# Sensorboard.net
KiCad netlist of a schematic drawn in Altium Designer
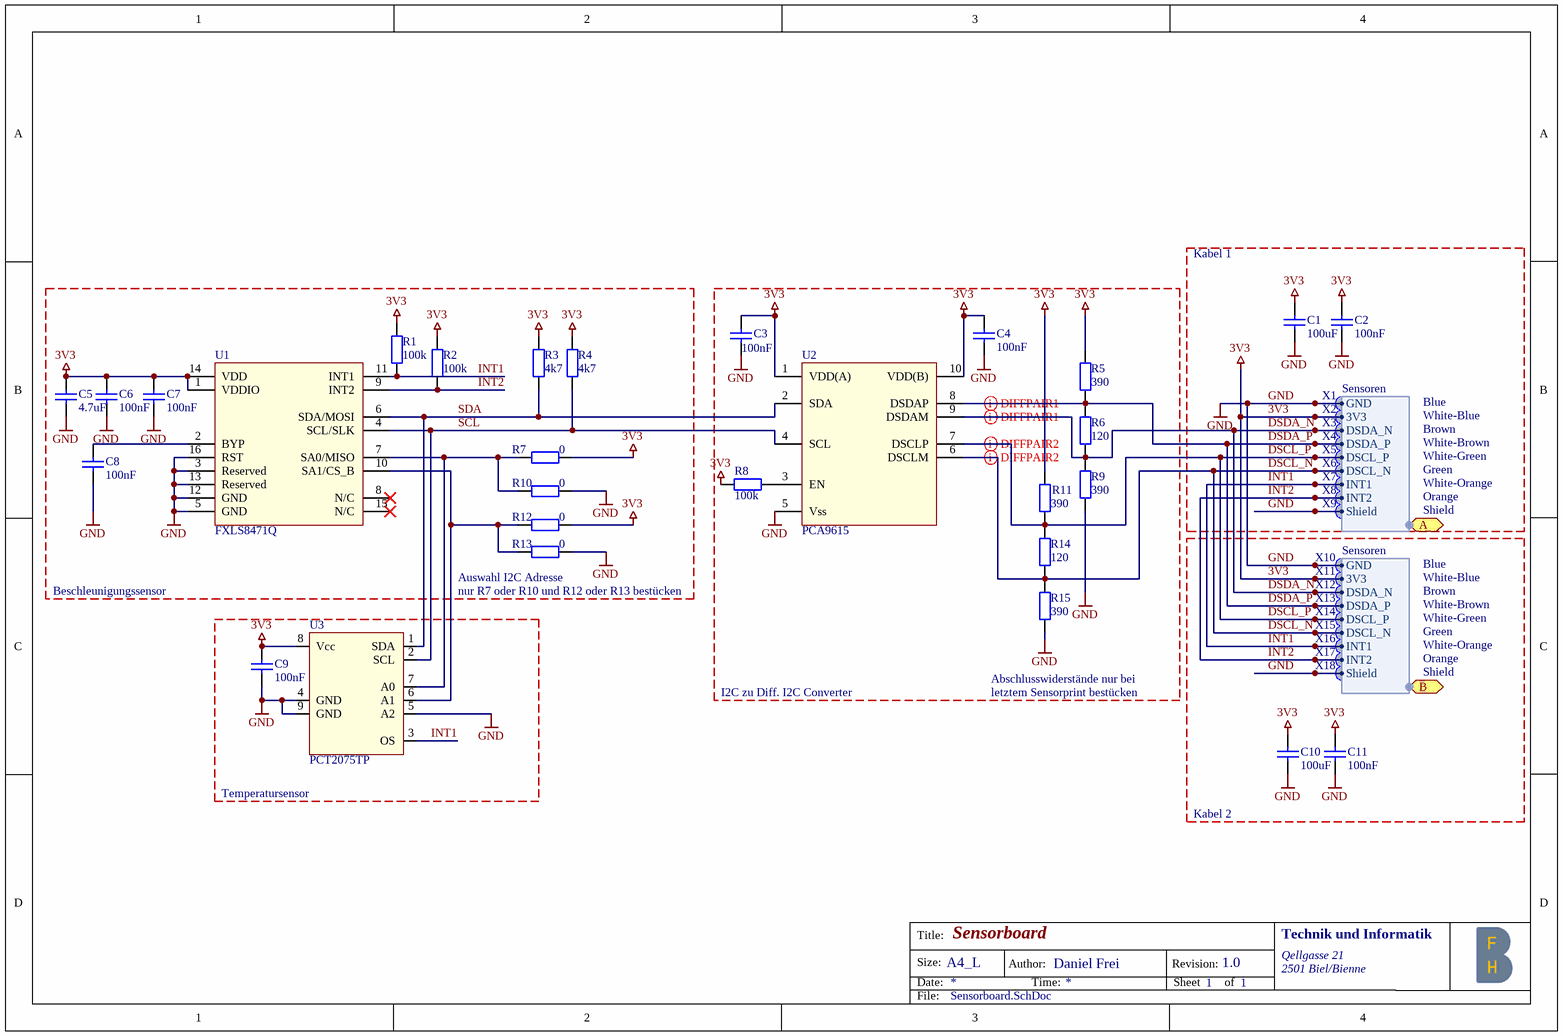
[diagram p0: Sensorboard.SchDoc]

(export (version "E")
  (design (tool "Eeschema 10.0.6"))
  (components
    (comp (ref "C1")
      (value "100uF")
      (footprint "RC_SMD_3D:CAPC3225[1210]X120")
      (description "Capacitor")
      (fields
        (field (name "MANUFACTURER") "Murata")
        (field (name "MANUFACTURER PART NUMBER") "GRM32ER61A107ME20L")
        (field (name "MODIFIED_BY") "BEP1")
      )
      (libsource (lib "RC_SMD_3D") (part "C"))
    )
    (comp (ref "C2")
      (value "100nF")
      (footprint "RC_SMD_3D:CAPC1005[0402]X50")
      (description "Capacitor")
      (fields (field (name "MODIFIED_BY") "BEP1"))
      (libsource (lib "RC_SMD_3D") (part "C"))
    )
    (comp (ref "C3")
      (value "100nF")
      (footprint "RC_SMD_3D:CAPC1005[0402]X50")
      (description "Capacitor")
      (fields (field (name "MODIFIED_BY") "BEP1"))
      (libsource (lib "RC_SMD_3D") (part "C"))
    )
    (comp (ref "C4")
      (value "100nF")
      (footprint "RC_SMD_3D:CAPC1005[0402]X50")
      (description "Capacitor")
      (fields (field (name "MODIFIED_BY") "BEP1"))
      (libsource (lib "RC_SMD_3D") (part "C"))
    )
    (comp (ref "C5")
      (value "4.7uF")
      (footprint "RC_SMD_3D:CAPC1608[0603]X80")
      (description "Capacitor")
      (fields
        (field (name "VOLTAGE") "10V")
        (field (name "MANUFACTURER") "Murata")
        (field (name "MODIFIED_BY") "BEP1")
      )
      (libsource (lib "RC_SMD_3D") (part "C"))
    )
    (comp (ref "C6")
      (value "100nF")
      (footprint "RC_SMD_3D:CAPC1005[0402]X50")
      (description "Capacitor")
      (fields (field (name "MODIFIED_BY") "BEP1"))
      (libsource (lib "RC_SMD_3D") (part "C"))
    )
    (comp (ref "C7")
      (value "100nF")
      (footprint "RC_SMD_3D:CAPC1005[0402]X50")
      (description "Capacitor")
      (fields (field (name "MODIFIED_BY") "BEP1"))
      (libsource (lib "RC_SMD_3D") (part "C"))
    )
    (comp (ref "C8")
      (value "100nF")
      (footprint "RC_SMD_3D:CAPC1005[0402]X50")
      (description "Capacitor")
      (fields (field (name "MODIFIED_BY") "BEP1"))
      (libsource (lib "RC_SMD_3D") (part "C"))
    )
    (comp (ref "C9")
      (value "100nF")
      (footprint "RC_SMD_3D:CAPC1005[0402]X50")
      (description "Capacitor")
      (fields (field (name "MODIFIED_BY") "BEP1"))
      (libsource (lib "RC_SMD_3D") (part "C"))
    )
    (comp (ref "C10")
      (value "100uF")
      (footprint "RC_SMD_3D:CAPC3225[1210]X120")
      (description "Capacitor")
      (fields
        (field (name "MANUFACTURER") "Murata")
        (field (name "MANUFACTURER PART NUMBER") "GRM32ER61A107ME20L")
        (field (name "MODIFIED_BY") "BEP1")
      )
      (libsource (lib "RC_SMD_3D") (part "C"))
    )
    (comp (ref "C11")
      (value "100nF")
      (footprint "RC_SMD_3D:CAPC1005[0402]X50")
      (description "Capacitor")
      (fields (field (name "MODIFIED_BY") "BEP1"))
      (libsource (lib "RC_SMD_3D") (part "C"))
    )
    (comp (ref "R1")
      (value "100k")
      (footprint "RC_SMD_3D:RESC1005[0402]X35")
      (description "Resistor")
      (fields (field (name "MODIFIED_BY") "BEP1"))
      (libsource (lib "RC_SMD_3D") (part "R"))
    )
    (comp (ref "R2")
      (value "100k")
      (footprint "RC_SMD_3D:RESC1005[0402]X35")
      (description "Resistor")
      (fields (field (name "MODIFIED_BY") "BEP1"))
      (libsource (lib "RC_SMD_3D") (part "R"))
    )
    (comp (ref "R3")
      (value "4k7")
      (footprint "RC_SMD_3D:RESC1005[0402]X35")
      (description "Resistor")
      (fields (field (name "MODIFIED_BY") "BEP1"))
      (libsource (lib "RC_SMD_3D") (part "R"))
    )
    (comp (ref "R4")
      (value "4k7")
      (footprint "RC_SMD_3D:RESC1005[0402]X35")
      (description "Resistor")
      (fields (field (name "MODIFIED_BY") "BEP1"))
      (libsource (lib "RC_SMD_3D") (part "R"))
    )
    (comp (ref "R5")
      (value "390")
      (footprint "RC_SMD_3D:RESC1005[0402]X35")
      (description "Resistor")
      (fields (field (name "MODIFIED_BY") "BEP1"))
      (libsource (lib "RC_SMD_3D") (part "R"))
    )
    (comp (ref "R6")
      (value "120")
      (footprint "RC_SMD_3D:RESC1005[0402]X35")
      (description "Resistor")
      (fields (field (name "MODIFIED_BY") "BEP1"))
      (libsource (lib "RC_SMD_3D") (part "R"))
    )
    (comp (ref "R7")
      (value "0")
      (footprint "RC_SMD_3D:RESC1005[0402]X35")
      (description "Resistor")
      (fields
        (field (name "MANUFACTURER") "Panasonic")
        (field (name "MANUFACTURER PART NUMBER") "ERJ-2GE0R00X")
        (field (name "MODIFIED_BY") "BEP1")
      )
      (libsource (lib "") (part "R_1"))
    )
    (comp (ref "R8")
      (value "100k")
      (footprint "RC_SMD_3D:RESC1005[0402]X35")
      (description "Resistor")
      (fields (field (name "MODIFIED_BY") "BEP1"))
      (libsource (lib "") (part "R_1"))
    )
    (comp (ref "R9")
      (value "390")
      (footprint "RC_SMD_3D:RESC1005[0402]X35")
      (description "Resistor")
      (fields (field (name "MODIFIED_BY") "BEP1"))
      (libsource (lib "RC_SMD_3D") (part "R"))
    )
    (comp (ref "R10")
      (value "0")
      (footprint "RC_SMD_3D:RESC1005[0402]X35")
      (description "Resistor")
      (fields
        (field (name "MANUFACTURER") "Panasonic")
        (field (name "MANUFACTURER PART NUMBER") "ERJ-2GE0R00X")
        (field (name "MODIFIED_BY") "BEP1")
      )
      (libsource (lib "") (part "R_1"))
    )
    (comp (ref "R11")
      (value "390")
      (footprint "RC_SMD_3D:RESC1005[0402]X35")
      (description "Resistor")
      (fields (field (name "MODIFIED_BY") "BEP1"))
      (libsource (lib "RC_SMD_3D") (part "R"))
    )
    (comp (ref "R12")
      (value "0")
      (footprint "RC_SMD_3D:RESC1005[0402]X35")
      (description "Resistor")
      (fields
        (field (name "MANUFACTURER") "Panasonic")
        (field (name "MANUFACTURER PART NUMBER") "ERJ-2GE0R00X")
        (field (name "MODIFIED_BY") "BEP1")
      )
      (libsource (lib "") (part "R_1"))
    )
    (comp (ref "R13")
      (value "0")
      (footprint "RC_SMD_3D:RESC1005[0402]X35")
      (description "Resistor")
      (fields
        (field (name "MANUFACTURER") "Panasonic")
        (field (name "MANUFACTURER PART NUMBER") "ERJ-2GE0R00X")
        (field (name "MODIFIED_BY") "BEP1")
      )
      (libsource (lib "") (part "R_1"))
    )
    (comp (ref "R14")
      (value "120")
      (footprint "RC_SMD_3D:RESC1005[0402]X35")
      (description "Resistor")
      (fields (field (name "MODIFIED_BY") "BEP1"))
      (libsource (lib "RC_SMD_3D") (part "R"))
    )
    (comp (ref "R15")
      (value "390")
      (footprint "RC_SMD_3D:RESC1005[0402]X35")
      (description "Resistor")
      (fields (field (name "MODIFIED_BY") "BEP1"))
      (libsource (lib "RC_SMD_3D") (part "R"))
    )
    (comp (ref "U1")
      (value "FXLS8471Q")
      (footprint "16 LEAD QFN")
      (description "3-Axis,  Linear Accelerometer")
      (fields (field (name "MANUFACTURER PART NUMBER") "FXLS8471QR1") (field (name "MANUFACTURER") "NXP"))
      (libsource (lib "Sensorboard_Library") (part "FXLS8471Q"))
    )
    (comp (ref "U2")
      (value "PCA9615")
      (footprint "TSSOP10")
      (description "differential I2C-bus buffer")
      (fields (field (name "MANUFACTURER PART NUMBER") "PCA9615DPJ") (field (name "MANUFACTURER") "NXP"))
      (libsource (lib "Sensorboard_Library") (part "PCA9615"))
    )
    (comp (ref "U3")
      (value "PCT2075TP")
      (footprint "HWSON8")
      (description "Temperature_Sensor")
      (fields (field (name "MANUFACTURER") "NXP") (field (name "MANUFACTURER PART NUMBER") "PCT2075TP,147"))
      (libsource (lib "Sensorboard_Library") (part "PCT2075TP"))
    )
    (comp (ref "X1")
      (value "Loch")
      (footprint "Loch")
      (description "Loch in Print um Kabel einzulöten")
      (libsource (lib "Sensorboard_Library") (part "Loch"))
    )
    (comp (ref "X2")
      (value "Loch")
      (footprint "Loch")
      (description "Loch in Print um Kabel einzulöten")
      (libsource (lib "Sensorboard_Library") (part "Loch"))
    )
    (comp (ref "X3")
      (value "Loch")
      (footprint "Loch")
      (description "Loch in Print um Kabel einzulöten")
      (libsource (lib "Sensorboard_Library") (part "Loch"))
    )
    (comp (ref "X4")
      (value "Loch")
      (footprint "Loch")
      (description "Loch in Print um Kabel einzulöten")
      (libsource (lib "Sensorboard_Library") (part "Loch"))
    )
    (comp (ref "X5")
      (value "Loch")
      (footprint "Loch")
      (description "Loch in Print um Kabel einzulöten")
      (libsource (lib "Sensorboard_Library") (part "Loch"))
    )
    (comp (ref "X6")
      (value "Loch")
      (footprint "Loch")
      (description "Loch in Print um Kabel einzulöten")
      (libsource (lib "Sensorboard_Library") (part "Loch"))
    )
    (comp (ref "X7")
      (value "Loch")
      (footprint "Loch")
      (description "Loch in Print um Kabel einzulöten")
      (libsource (lib "Sensorboard_Library") (part "Loch"))
    )
    (comp (ref "X8")
      (value "Loch")
      (footprint "Loch")
      (description "Loch in Print um Kabel einzulöten")
      (libsource (lib "Sensorboard_Library") (part "Loch"))
    )
    (comp (ref "X9")
      (value "Loch")
      (footprint "Loch")
      (description "Loch in Print um Kabel einzulöten")
      (libsource (lib "Sensorboard_Library") (part "Loch"))
    )
    (comp (ref "X10")
      (value "Loch")
      (footprint "Loch")
      (description "Loch in Print um Kabel einzulöten")
      (libsource (lib "Sensorboard_Library") (part "Loch"))
    )
    (comp (ref "X11")
      (value "Loch")
      (footprint "Loch")
      (description "Loch in Print um Kabel einzulöten")
      (libsource (lib "Sensorboard_Library") (part "Loch"))
    )
    (comp (ref "X12")
      (value "Loch")
      (footprint "Loch")
      (description "Loch in Print um Kabel einzulöten")
      (libsource (lib "Sensorboard_Library") (part "Loch"))
    )
    (comp (ref "X13")
      (value "Loch")
      (footprint "Loch")
      (description "Loch in Print um Kabel einzulöten")
      (libsource (lib "Sensorboard_Library") (part "Loch"))
    )
    (comp (ref "X14")
      (value "Loch")
      (footprint "Loch")
      (description "Loch in Print um Kabel einzulöten")
      (libsource (lib "Sensorboard_Library") (part "Loch"))
    )
    (comp (ref "X15")
      (value "Loch")
      (footprint "Loch")
      (description "Loch in Print um Kabel einzulöten")
      (libsource (lib "Sensorboard_Library") (part "Loch"))
    )
    (comp (ref "X16")
      (value "Loch")
      (footprint "Loch")
      (description "Loch in Print um Kabel einzulöten")
      (libsource (lib "Sensorboard_Library") (part "Loch"))
    )
    (comp (ref "X17")
      (value "Loch")
      (footprint "Loch")
      (description "Loch in Print um Kabel einzulöten")
      (libsource (lib "Sensorboard_Library") (part "Loch"))
    )
    (comp (ref "X18")
      (value "Loch")
      (footprint "Loch")
      (description "Loch in Print um Kabel einzulöten")
      (libsource (lib "Sensorboard_Library") (part "Loch"))
    )
  )
  (nets
    (net (code "2") (name "/DSCL_N") (class "Default")
      (node (ref "R14") (pin "1") (pintype "passive"))
      (node (ref "R15") (pin "2") (pintype "passive"))
      (node (ref "U2") (pin "6") (pinfunction "DSCLM_6") (pintype "passive"))
      (node (ref "X15") (pin "1") (pinfunction "1_1") (pintype "passive"))
      (node (ref "X6") (pin "1") (pinfunction "1_1") (pintype "passive"))
    )
    (net (code "3") (name "/DSCL_P") (class "Default")
      (node (ref "R11") (pin "1") (pintype "passive"))
      (node (ref "R14") (pin "2") (pintype "passive"))
      (node (ref "U2") (pin "7") (pinfunction "DSCLP_7") (pintype "passive"))
      (node (ref "X14") (pin "1") (pinfunction "1_1") (pintype "passive"))
      (node (ref "X5") (pin "1") (pinfunction "1_1") (pintype "passive"))
    )
    (net (code "4") (name "/DSDA_N") (class "Default")
      (node (ref "R6") (pin "1") (pintype "passive"))
      (node (ref "R9") (pin "2") (pintype "passive"))
      (node (ref "U2") (pin "9") (pinfunction "DSDAM_9") (pintype "passive"))
      (node (ref "X12") (pin "1") (pinfunction "1_1") (pintype "passive"))
      (node (ref "X3") (pin "1") (pinfunction "1_1") (pintype "passive"))
    )
    (net (code "5") (name "/DSDA_P") (class "Default")
      (node (ref "R5") (pin "1") (pintype "passive"))
      (node (ref "R6") (pin "2") (pintype "passive"))
      (node (ref "U2") (pin "8") (pinfunction "DSDAP_8") (pintype "passive"))
      (node (ref "X13") (pin "1") (pinfunction "1_1") (pintype "passive"))
      (node (ref "X4") (pin "1") (pinfunction "1_1") (pintype "passive"))
    )
    (net (code "6") (name "/INT1") (class "Default")
      (node (ref "R1") (pin "1") (pintype "passive"))
      (node (ref "U1") (pin "11") (pinfunction "INT1_11") (pintype "passive"))
      (node (ref "U3") (pin "3") (pinfunction "OS_3") (pintype "passive"))
      (node (ref "X16") (pin "1") (pinfunction "1_1") (pintype "passive"))
      (node (ref "X7") (pin "1") (pinfunction "1_1") (pintype "passive"))
    )
    (net (code "7") (name "/INT2") (class "Default")
      (node (ref "R2") (pin "1") (pintype "passive"))
      (node (ref "U1") (pin "9") (pinfunction "INT2_9") (pintype "passive"))
      (node (ref "X17") (pin "1") (pinfunction "1_1") (pintype "passive"))
      (node (ref "X8") (pin "1") (pinfunction "1_1") (pintype "passive"))
    )
    (net (code "8") (name "/SCL") (class "Default")
      (node (ref "R4") (pin "1") (pintype "passive"))
      (node (ref "U1") (pin "4") (pinfunction "SCL/SLK_4") (pintype "passive"))
      (node (ref "U2") (pin "4") (pinfunction "SCL_4") (pintype "passive"))
      (node (ref "U3") (pin "2") (pinfunction "SCL_2") (pintype "passive"))
    )
    (net (code "9") (name "/SDA") (class "Default")
      (node (ref "R3") (pin "1") (pintype "passive"))
      (node (ref "U1") (pin "6") (pinfunction "SDA/MOSI_6") (pintype "passive"))
      (node (ref "U2") (pin "2") (pinfunction "SDA_2") (pintype "passive"))
      (node (ref "U3") (pin "1") (pinfunction "SDA_1") (pintype "passive"))
    )
    (net (code "11") (name "3V3") (class "Default")
      (node (ref "C1") (pin "2") (pintype "passive"))
      (node (ref "C10") (pin "2") (pintype "passive"))
      (node (ref "C11") (pin "2") (pintype "passive"))
      (node (ref "C2") (pin "2") (pintype "passive"))
      (node (ref "C3") (pin "2") (pintype "passive"))
      (node (ref "C4") (pin "2") (pintype "passive"))
      (node (ref "C5") (pin "2") (pintype "passive"))
      (node (ref "C6") (pin "2") (pintype "passive"))
      (node (ref "C7") (pin "2") (pintype "passive"))
      (node (ref "C9") (pin "2") (pintype "passive"))
      (node (ref "R1") (pin "2") (pintype "passive"))
      (node (ref "R11") (pin "2") (pintype "passive"))
      (node (ref "R12") (pin "2") (pintype "passive"))
      (node (ref "R2") (pin "2") (pintype "passive"))
      (node (ref "R3") (pin "2") (pintype "passive"))
      (node (ref "R4") (pin "2") (pintype "passive"))
      (node (ref "R5") (pin "2") (pintype "passive"))
      (node (ref "R7") (pin "2") (pintype "passive"))
      (node (ref "R8") (pin "1") (pintype "passive"))
      (node (ref "U1") (pin "1") (pinfunction "VDDIO_1") (pintype "passive"))
      (node (ref "U1") (pin "14") (pinfunction "VDD_14") (pintype "passive"))
      (node (ref "U2") (pin "1") (pinfunction "VDD(A)_1") (pintype "passive"))
      (node (ref "U2") (pin "10") (pinfunction "VDD(B)_10") (pintype "passive"))
      (node (ref "U3") (pin "8") (pinfunction "Vcc_8") (pintype "passive"))
      (node (ref "X11") (pin "1") (pinfunction "1_1") (pintype "passive"))
      (node (ref "X2") (pin "1") (pinfunction "1_1") (pintype "passive"))
    )
    (net (code "12") (name "GND") (class "Default")
      (node (ref "C1") (pin "1") (pintype "passive"))
      (node (ref "C10") (pin "1") (pintype "passive"))
      (node (ref "C11") (pin "1") (pintype "passive"))
      (node (ref "C2") (pin "1") (pintype "passive"))
      (node (ref "C3") (pin "1") (pintype "passive"))
      (node (ref "C4") (pin "1") (pintype "passive"))
      (node (ref "C5") (pin "1") (pintype "passive"))
      (node (ref "C6") (pin "1") (pintype "passive"))
      (node (ref "C7") (pin "1") (pintype "passive"))
      (node (ref "C8") (pin "1") (pintype "passive"))
      (node (ref "C9") (pin "1") (pintype "passive"))
      (node (ref "R10") (pin "2") (pintype "passive"))
      (node (ref "R13") (pin "2") (pintype "passive"))
      (node (ref "R15") (pin "1") (pintype "passive"))
      (node (ref "R9") (pin "1") (pintype "passive"))
      (node (ref "U1") (pin "12") (pinfunction "GND_12") (pintype "passive"))
      (node (ref "U1") (pin "13") (pinfunction "Reserved_13") (pintype "passive"))
      (node (ref "U1") (pin "16") (pinfunction "RST_16") (pintype "passive"))
      (node (ref "U1") (pin "3") (pinfunction "Reserved_3") (pintype "passive"))
      (node (ref "U1") (pin "5") (pinfunction "GND_5") (pintype "passive"))
      (node (ref "U2") (pin "5") (pinfunction "Vss_5") (pintype "passive"))
      (node (ref "U3") (pin "4") (pinfunction "GND_4") (pintype "passive"))
      (node (ref "U3") (pin "5") (pinfunction "A2_5") (pintype "passive"))
      (node (ref "U3") (pin "9") (pinfunction "GND_9") (pintype "passive"))
      (node (ref "X1") (pin "1") (pinfunction "1_1") (pintype "passive"))
      (node (ref "X10") (pin "1") (pinfunction "1_1") (pintype "passive"))
      (node (ref "X18") (pin "1") (pinfunction "1_1") (pintype "passive"))
      (node (ref "X9") (pin "1") (pinfunction "1_1") (pintype "passive"))
    )
    (net (code "13") (name "Net-(U1-BYP)") (class "Default")
      (node (ref "C8") (pin "2") (pintype "passive"))
      (node (ref "U1") (pin "2") (pinfunction "BYP_2") (pintype "passive"))
    )
    (net (code "14") (name "Net-(U1-SA0{slash}MISO)") (class "Default")
      (node (ref "R10") (pin "1") (pintype "passive"))
      (node (ref "R7") (pin "1") (pintype "passive"))
      (node (ref "U1") (pin "7") (pinfunction "SA0/MISO_7") (pintype "passive"))
      (node (ref "U3") (pin "7") (pinfunction "A0_7") (pintype "passive"))
    )
    (net (code "15") (name "Net-(U1-SA1{slash}CS_B)") (class "Default")
      (node (ref "R12") (pin "1") (pintype "passive"))
      (node (ref "R13") (pin "1") (pintype "passive"))
      (node (ref "U1") (pin "10") (pinfunction "SA1/CS_B_10") (pintype "passive"))
      (node (ref "U3") (pin "6") (pinfunction "A1_6") (pintype "passive"))
    )
    (net (code "16") (name "Net-(U2-EN)") (class "Default")
      (node (ref "R8") (pin "2") (pintype "passive"))
      (node (ref "U2") (pin "3") (pinfunction "EN_3") (pintype "passive"))
    )
    (net (code "17") (name "unconnected-(U1-N{slash}C-Pad8)") (class "Default")
      (node (ref "U1") (pin "8") (pinfunction "N/C_8") (pintype "passive+no_connect"))
    )
    (net (code "18") (name "unconnected-(U1-N{slash}C-Pad15)") (class "Default")
      (node (ref "U1") (pin "15") (pinfunction "N/C_15") (pintype "passive+no_connect"))
    )
  )
)
